# ProProject_DevBoard_20240716_2024-07-17.net
KiCad netlist of a schematic drawn in EasyEDA Pro
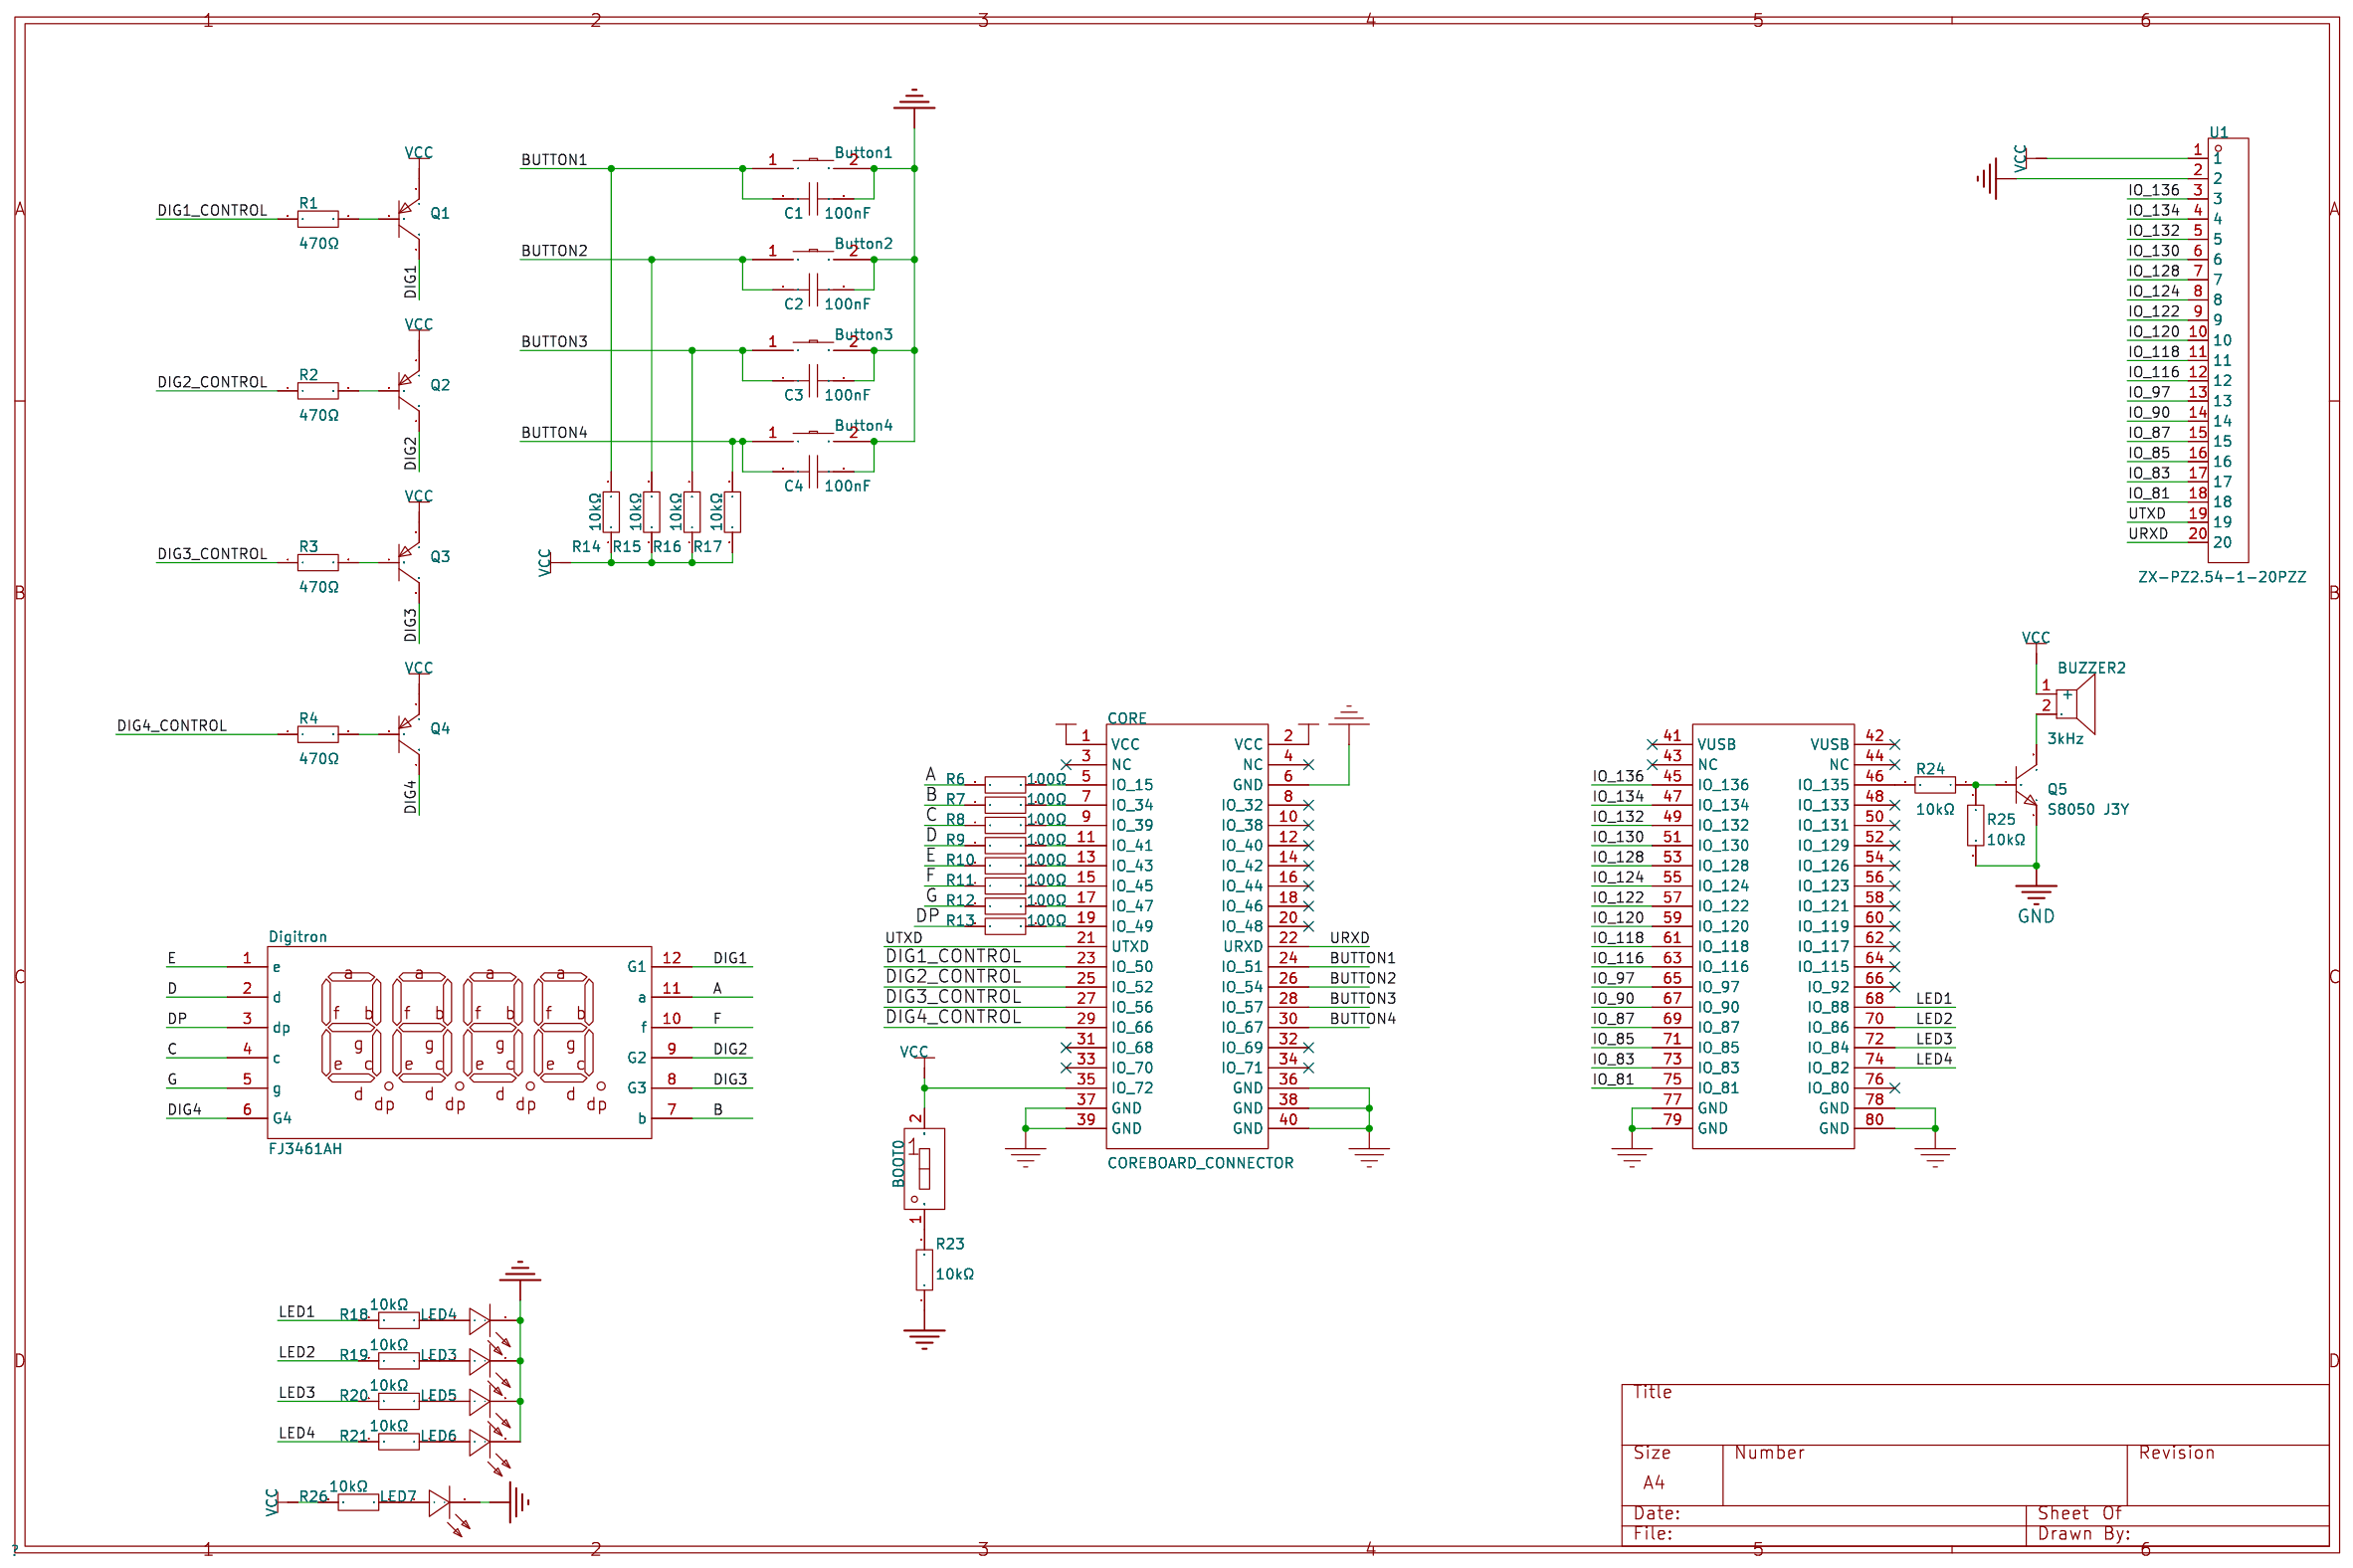
[diagram p0: schematic sheet]

(export (version "E")
  (design (tool "Eeschema 10.0.6"))
  (components
    (comp (ref "BOOT0")
      (value "DSIC01LS-P")
      (footprint "easyedapro:SW-SMD_2P-L3.5-W6.2-P2.54-LS9.8")
      (description "类型:平拨,凸起式;电路结构:单刀单掷;开关位数:1位;额定电流:25mA;额定电压:24V;使用寿命:3千次;颜色:黑色;")
      (fields (field (name "Manufacturer") "XKB Connectivity(中国星坤)"))
      (libsource (lib "easyedapro") (part "DSIC01LS-P_C600988"))
    )
    (comp (ref "Button1")
      (value "TS-1101-C-W")
      (footprint "easyedapro:SW-SMD_L6.0-W3.3-LS8.0")
      (fields (field (name "Manufacturer") "XKB Connectivity(中国星坤)"))
      (libsource (lib "easyedapro") (part "TS-1101-C-W"))
    )
    (comp (ref "Button2")
      (value "TS-1101-C-W")
      (footprint "easyedapro:SW-SMD_L6.0-W3.3-LS8.0")
      (fields (field (name "Manufacturer") "XKB Connectivity(中国星坤)"))
      (libsource (lib "easyedapro") (part "TS-1101-C-W"))
    )
    (comp (ref "Button3")
      (value "TS-1101-C-W")
      (footprint "easyedapro:SW-SMD_L6.0-W3.3-LS8.0")
      (fields (field (name "Manufacturer") "XKB Connectivity(中国星坤)"))
      (libsource (lib "easyedapro") (part "TS-1101-C-W"))
    )
    (comp (ref "Button4")
      (value "TS-1101-C-W")
      (footprint "easyedapro:SW-SMD_L6.0-W3.3-LS8.0")
      (fields (field (name "Manufacturer") "XKB Connectivity(中国星坤)"))
      (libsource (lib "easyedapro") (part "TS-1101-C-W"))
    )
    (comp (ref "BUZZER2")
      (value "3kHz")
      (footprint "easyedapro:BUZ-TH_BD9.6-P5.00-D0.7-FD")
      (description "驱动方式:有源(内含驱动线路);构造类型:电磁式;频率:3kHz;声压(SPL):85dB;")
      (fields (field (name "Manufacturer Part") "HNB09A05") (field (name "Manufacturer") "华能"))
      (libsource (lib "easyedapro") (part "HNB09A05"))
    )
    (comp (ref "C1")
      (value "100nF")
      (footprint "easyedapro:C0603")
      (description "容值:100nF;精度:±10%;额定电压:50V;材质(温度系数):X7R;")
      (fields
        (field (name "Manufacturer Part") "CC0603KRX7R9BB104")
        (field (name "Manufacturer") "YAGEO(国巨)")
      )
      (libsource (lib "easyedapro") (part "CC0603KRX7R9BB104"))
    )
    (comp (ref "C2")
      (value "100nF")
      (footprint "easyedapro:C0603")
      (description "容值:100nF;精度:±10%;额定电压:50V;材质(温度系数):X7R;")
      (fields
        (field (name "Manufacturer Part") "CC0603KRX7R9BB104")
        (field (name "Manufacturer") "YAGEO(国巨)")
      )
      (libsource (lib "easyedapro") (part "CC0603KRX7R9BB104"))
    )
    (comp (ref "C3")
      (value "100nF")
      (footprint "easyedapro:C0603")
      (description "容值:100nF;精度:±10%;额定电压:50V;材质(温度系数):X7R;")
      (fields
        (field (name "Manufacturer Part") "CC0603KRX7R9BB104")
        (field (name "Manufacturer") "YAGEO(国巨)")
      )
      (libsource (lib "easyedapro") (part "CC0603KRX7R9BB104"))
    )
    (comp (ref "C4")
      (value "100nF")
      (footprint "easyedapro:C0603")
      (description "容值:100nF;精度:±10%;额定电压:50V;材质(温度系数):X7R;")
      (fields
        (field (name "Manufacturer Part") "CC0603KRX7R9BB104")
        (field (name "Manufacturer") "YAGEO(国巨)")
      )
      (libsource (lib "easyedapro") (part "CC0603KRX7R9BB104"))
    )
    (comp (ref "CORE")
      (value "COREBOARD_CONNECTOR")
      (libsource (lib "easyedapro") (part "COREBOARD_CONNECTOR"))
    )
    (comp (ref "Digitron")
      (value "FJ3461AH")
      (footprint "easyedapro:LED-SEG-TH_12P-L30.0-W14.0-P2.54-S10.16-BL")
      (description "数码管位数:4位;功耗:-;发光颜色:红色;LED极性:共阴极;数字/字母大小(英寸):0.36;")
      (fields (field (name "Manufacturer") "志浩"))
      (libsource (lib "easyedapro") (part "FJ3461AH"))
    )
    (comp (ref "LED3")
      (value "NCD0805B2")
      (footprint "easyedapro:LED0805-R-RD")
      (fields (field (name "Manufacturer") "国星光电"))
      (libsource (lib "easyedapro") (part "FC-A2012BK-470H2"))
    )
    (comp (ref "LED4")
      (value "NCD0805B2")
      (footprint "easyedapro:LED0805-R-RD")
      (fields (field (name "Manufacturer") "国星光电"))
      (libsource (lib "easyedapro") (part "FC-A2012BK-470H2"))
    )
    (comp (ref "LED5")
      (value "NCD0805B2")
      (footprint "easyedapro:LED0805-R-RD")
      (fields (field (name "Manufacturer") "国星光电"))
      (libsource (lib "easyedapro") (part "FC-A2012BK-470H2"))
    )
    (comp (ref "LED6")
      (value "NCD0805B2")
      (footprint "easyedapro:LED0805-R-RD")
      (fields (field (name "Manufacturer") "国星光电"))
      (libsource (lib "easyedapro") (part "FC-A2012BK-470H2"))
    )
    (comp (ref "LED7")
      (value "NCD0805B2")
      (footprint "easyedapro:LED0805-R-RD")
      (fields (field (name "Manufacturer") "国星光电"))
      (libsource (lib "easyedapro") (part "FC-A2012BK-470H2"))
    )
    (comp (ref "Q1")
      (value "~")
      (footprint "easyedapro:S8550P_SOT")
      (libsource (lib "easyedapro") (part "PNP"))
    )
    (comp (ref "Q2")
      (value "~")
      (footprint "easyedapro:S8550P_SOT")
      (libsource (lib "easyedapro") (part "PNP"))
    )
    (comp (ref "Q3")
      (value "~")
      (footprint "easyedapro:S8550P_SOT")
      (libsource (lib "easyedapro") (part "PNP"))
    )
    (comp (ref "Q4")
      (value "~")
      (footprint "easyedapro:S8550P_SOT")
      (libsource (lib "easyedapro") (part "PNP"))
    )
    (comp (ref "Q5")
      (value "S8050 J3Y")
      (footprint "easyedapro:SOT-23-3_L3.0-W1.7-P0.95-LS2.9-BR")
      (description "晶体管类型:NPN;集射极击穿电压(Vceo):25V;集电极电流(Ic):500mA;功率(Pd):300mW;直流电流增益(hFE@Ic,Vce):200@50mA,1V;")
      (fields (field (name "Manufacturer") "CJ(江苏长电/长晶)"))
      (libsource (lib "easyedapro") (part "S8050_C2146"))
    )
    (comp (ref "R1")
      (value "470Ω")
      (footprint "easyedapro:R0603")
      (description "电阻类型:厚膜电阻;阻值:470Ω;精度:±1%;功率:100mW;最大工作电压:75V;温度系数:±100ppm/°C;")
      (fields
        (field (name "Manufacturer Part") "0603WAF4700T5E")
        (field (name "Manufacturer") "UNI-ROYAL(厚声)")
      )
      (libsource (lib "easyedapro") (part "0603WAF4700T5E"))
    )
    (comp (ref "R2")
      (value "470Ω")
      (footprint "easyedapro:R0603")
      (description "电阻类型:厚膜电阻;阻值:470Ω;精度:±1%;功率:100mW;最大工作电压:75V;温度系数:±100ppm/°C;")
      (fields
        (field (name "Manufacturer Part") "0603WAF4700T5E")
        (field (name "Manufacturer") "UNI-ROYAL(厚声)")
      )
      (libsource (lib "easyedapro") (part "0603WAF4700T5E"))
    )
    (comp (ref "R3")
      (value "470Ω")
      (footprint "easyedapro:R0603")
      (description "电阻类型:厚膜电阻;阻值:470Ω;精度:±1%;功率:100mW;最大工作电压:75V;温度系数:±100ppm/°C;")
      (fields
        (field (name "Manufacturer Part") "0603WAF4700T5E")
        (field (name "Manufacturer") "UNI-ROYAL(厚声)")
      )
      (libsource (lib "easyedapro") (part "0603WAF4700T5E"))
    )
    (comp (ref "R4")
      (value "470Ω")
      (footprint "easyedapro:R0603")
      (description "电阻类型:厚膜电阻;阻值:470Ω;精度:±1%;功率:100mW;最大工作电压:75V;温度系数:±100ppm/°C;")
      (fields
        (field (name "Manufacturer Part") "0603WAF4700T5E")
        (field (name "Manufacturer") "UNI-ROYAL(厚声)")
      )
      (libsource (lib "easyedapro") (part "0603WAF4700T5E"))
    )
    (comp (ref "R6")
      (value "100Ω")
      (footprint "easyedapro:R0603")
      (description "电阻类型:厚膜电阻;阻值:100Ω;精度:±1%;功率:100mW;最大工作电压:75V;温度系数:±200ppm/°C;")
      (fields
        (field (name "Manufacturer Part") "0603WAF1000T5E")
        (field (name "Manufacturer") "UNI-ROYAL(厚声)")
      )
      (libsource (lib "easyedapro") (part "0603WAF1000T5E"))
    )
    (comp (ref "R7")
      (value "100Ω")
      (footprint "easyedapro:R0603")
      (description "电阻类型:厚膜电阻;阻值:100Ω;精度:±1%;功率:100mW;最大工作电压:75V;温度系数:±200ppm/°C;")
      (fields
        (field (name "Manufacturer Part") "0603WAF1000T5E")
        (field (name "Manufacturer") "UNI-ROYAL(厚声)")
      )
      (libsource (lib "easyedapro") (part "0603WAF1000T5E"))
    )
    (comp (ref "R8")
      (value "100Ω")
      (footprint "easyedapro:R0603")
      (description "电阻类型:厚膜电阻;阻值:100Ω;精度:±1%;功率:100mW;最大工作电压:75V;温度系数:±200ppm/°C;")
      (fields
        (field (name "Manufacturer Part") "0603WAF1000T5E")
        (field (name "Manufacturer") "UNI-ROYAL(厚声)")
      )
      (libsource (lib "easyedapro") (part "0603WAF1000T5E"))
    )
    (comp (ref "R9")
      (value "100Ω")
      (footprint "easyedapro:R0603")
      (description "电阻类型:厚膜电阻;阻值:100Ω;精度:±1%;功率:100mW;最大工作电压:75V;温度系数:±200ppm/°C;")
      (fields
        (field (name "Manufacturer Part") "0603WAF1000T5E")
        (field (name "Manufacturer") "UNI-ROYAL(厚声)")
      )
      (libsource (lib "easyedapro") (part "0603WAF1000T5E"))
    )
    (comp (ref "R10")
      (value "100Ω")
      (footprint "easyedapro:R0603")
      (description "电阻类型:厚膜电阻;阻值:100Ω;精度:±1%;功率:100mW;最大工作电压:75V;温度系数:±200ppm/°C;")
      (fields
        (field (name "Manufacturer Part") "0603WAF1000T5E")
        (field (name "Manufacturer") "UNI-ROYAL(厚声)")
      )
      (libsource (lib "easyedapro") (part "0603WAF1000T5E"))
    )
    (comp (ref "R11")
      (value "100Ω")
      (footprint "easyedapro:R0603")
      (description "电阻类型:厚膜电阻;阻值:100Ω;精度:±1%;功率:100mW;最大工作电压:75V;温度系数:±200ppm/°C;")
      (fields
        (field (name "Manufacturer Part") "0603WAF1000T5E")
        (field (name "Manufacturer") "UNI-ROYAL(厚声)")
      )
      (libsource (lib "easyedapro") (part "0603WAF1000T5E"))
    )
    (comp (ref "R12")
      (value "100Ω")
      (footprint "easyedapro:R0603")
      (description "电阻类型:厚膜电阻;阻值:100Ω;精度:±1%;功率:100mW;最大工作电压:75V;温度系数:±200ppm/°C;")
      (fields
        (field (name "Manufacturer Part") "0603WAF1000T5E")
        (field (name "Manufacturer") "UNI-ROYAL(厚声)")
      )
      (libsource (lib "easyedapro") (part "0603WAF1000T5E"))
    )
    (comp (ref "R13")
      (value "100Ω")
      (footprint "easyedapro:R0603")
      (description "电阻类型:厚膜电阻;阻值:100Ω;精度:±1%;功率:100mW;最大工作电压:75V;温度系数:±200ppm/°C;")
      (fields
        (field (name "Manufacturer Part") "0603WAF1000T5E")
        (field (name "Manufacturer") "UNI-ROYAL(厚声)")
      )
      (libsource (lib "easyedapro") (part "0603WAF1000T5E"))
    )
    (comp (ref "R14")
      (value "10kΩ")
      (footprint "easyedapro:R0603")
      (description "电阻类型:厚膜电阻;阻值:10kΩ;精度:±1%;功率:100mW;最大工作电压:75V;温度系数:±100ppm/°C;")
      (fields
        (field (name "Manufacturer Part") "0603WAF1002T5E")
        (field (name "Manufacturer") "UNI-ROYAL(厚声)")
      )
      (libsource (lib "easyedapro") (part "0603WAF1002T5E"))
    )
    (comp (ref "R15")
      (value "10kΩ")
      (footprint "easyedapro:R0603")
      (description "电阻类型:厚膜电阻;阻值:10kΩ;精度:±1%;功率:100mW;最大工作电压:75V;温度系数:±100ppm/°C;")
      (fields
        (field (name "Manufacturer Part") "0603WAF1002T5E")
        (field (name "Manufacturer") "UNI-ROYAL(厚声)")
      )
      (libsource (lib "easyedapro") (part "0603WAF1002T5E"))
    )
    (comp (ref "R16")
      (value "10kΩ")
      (footprint "easyedapro:R0603")
      (description "电阻类型:厚膜电阻;阻值:10kΩ;精度:±1%;功率:100mW;最大工作电压:75V;温度系数:±100ppm/°C;")
      (fields
        (field (name "Manufacturer Part") "0603WAF1002T5E")
        (field (name "Manufacturer") "UNI-ROYAL(厚声)")
      )
      (libsource (lib "easyedapro") (part "0603WAF1002T5E"))
    )
    (comp (ref "R17")
      (value "10kΩ")
      (footprint "easyedapro:R0603")
      (description "电阻类型:厚膜电阻;阻值:10kΩ;精度:±1%;功率:100mW;最大工作电压:75V;温度系数:±100ppm/°C;")
      (fields
        (field (name "Manufacturer Part") "0603WAF1002T5E")
        (field (name "Manufacturer") "UNI-ROYAL(厚声)")
      )
      (libsource (lib "easyedapro") (part "0603WAF1002T5E"))
    )
    (comp (ref "R18")
      (value "10kΩ")
      (footprint "easyedapro:R0603")
      (description "电阻类型:厚膜电阻;阻值:10kΩ;精度:±1%;功率:100mW;最大工作电压:75V;温度系数:±100ppm/°C;")
      (fields
        (field (name "Manufacturer Part") "0603WAF1002T5E")
        (field (name "Manufacturer") "UNI-ROYAL(厚声)")
      )
      (libsource (lib "easyedapro") (part "0603WAF1002T5E"))
    )
    (comp (ref "R19")
      (value "10kΩ")
      (footprint "easyedapro:R0603")
      (description "电阻类型:厚膜电阻;阻值:10kΩ;精度:±1%;功率:100mW;最大工作电压:75V;温度系数:±100ppm/°C;")
      (fields
        (field (name "Manufacturer Part") "0603WAF1002T5E")
        (field (name "Manufacturer") "UNI-ROYAL(厚声)")
      )
      (libsource (lib "easyedapro") (part "0603WAF1002T5E"))
    )
    (comp (ref "R20")
      (value "10kΩ")
      (footprint "easyedapro:R0603")
      (description "电阻类型:厚膜电阻;阻值:10kΩ;精度:±1%;功率:100mW;最大工作电压:75V;温度系数:±100ppm/°C;")
      (fields
        (field (name "Manufacturer Part") "0603WAF1002T5E")
        (field (name "Manufacturer") "UNI-ROYAL(厚声)")
      )
      (libsource (lib "easyedapro") (part "0603WAF1002T5E"))
    )
    (comp (ref "R21")
      (value "10kΩ")
      (footprint "easyedapro:R0603")
      (description "电阻类型:厚膜电阻;阻值:10kΩ;精度:±1%;功率:100mW;最大工作电压:75V;温度系数:±100ppm/°C;")
      (fields
        (field (name "Manufacturer Part") "0603WAF1002T5E")
        (field (name "Manufacturer") "UNI-ROYAL(厚声)")
      )
      (libsource (lib "easyedapro") (part "0603WAF1002T5E"))
    )
    (comp (ref "R23")
      (value "10kΩ")
      (footprint "easyedapro:R0603")
      (description "电阻类型:厚膜电阻;阻值:10kΩ;精度:±1%;功率:100mW;最大工作电压:75V;温度系数:±100ppm/°C;")
      (fields
        (field (name "Manufacturer Part") "0603WAF1002T5E")
        (field (name "Manufacturer") "UNI-ROYAL(厚声)")
      )
      (libsource (lib "easyedapro") (part "0603WAF1002T5E"))
    )
    (comp (ref "R24")
      (value "10kΩ")
      (footprint "easyedapro:R0805")
      (description "阻值:10kΩ;精度:±1%;功率:125mW;温度系数:±100ppm/°C;电阻类型:厚膜电阻;")
      (fields
        (field (name "Manufacturer Part") "0805W8F1002T5E")
        (field (name "Manufacturer") "UNI-ROYAL(厚声)")
      )
      (libsource (lib "easyedapro") (part "0805W8F1002T5E"))
    )
    (comp (ref "R25")
      (value "10kΩ")
      (footprint "easyedapro:R0805")
      (description "阻值:10kΩ;精度:±1%;功率:125mW;温度系数:±100ppm/°C;电阻类型:厚膜电阻;")
      (fields
        (field (name "Manufacturer Part") "0805W8F1002T5E")
        (field (name "Manufacturer") "UNI-ROYAL(厚声)")
      )
      (libsource (lib "easyedapro") (part "0805W8F1002T5E"))
    )
    (comp (ref "R26")
      (value "10kΩ")
      (footprint "easyedapro:R0603")
      (description "电阻类型:厚膜电阻;阻值:10kΩ;精度:±1%;功率:100mW;最大工作电压:75V;温度系数:±100ppm/°C;")
      (fields
        (field (name "Manufacturer Part") "0603WAF1002T5E")
        (field (name "Manufacturer") "UNI-ROYAL(厚声)")
      )
      (libsource (lib "easyedapro") (part "0603WAF1002T5E"))
    )
    (comp (ref "U1")
      (value "ZX-PZ2.54-1-20PZZ")
      (footprint "easyedapro:HDR-TH_20P-P2.54-V-M")
      (fields (field (name "Manufacturer") "Megastar(兆星)"))
      (libsource (lib "easyedapro") (part "ZX-PZ2.54-1-20PZZ"))
    )
  )
  (nets
    (net (code "1") (name "/A") (class "Default")
      (node (ref "Digitron") (pin "11") (pinfunction "a_11") (pintype "input"))
      (node (ref "R6") (pin "1") (pinfunction "1_1") (pintype "input"))
    )
    (net (code "2") (name "/B") (class "Default")
      (node (ref "Digitron") (pin "7") (pinfunction "b_7") (pintype "input"))
      (node (ref "R7") (pin "1") (pinfunction "1_1") (pintype "input"))
    )
    (net (code "3") (name "/BUTTON1") (class "Default")
      (node (ref "Button1") (pin "1") (pinfunction "1_1") (pintype "unspecified"))
      (node (ref "C1") (pin "1") (pinfunction "1_1") (pintype "unspecified"))
      (node (ref "CORE") (pin "24") (pinfunction "IO_51_24") (pintype "unspecified"))
      (node (ref "R14") (pin "2") (pinfunction "2_2") (pintype "input"))
    )
    (net (code "4") (name "/BUTTON2") (class "Default")
      (node (ref "Button2") (pin "1") (pinfunction "1_1") (pintype "unspecified"))
      (node (ref "C2") (pin "1") (pinfunction "1_1") (pintype "unspecified"))
      (node (ref "CORE") (pin "26") (pinfunction "IO_54_26") (pintype "unspecified"))
      (node (ref "R15") (pin "2") (pinfunction "2_2") (pintype "input"))
    )
    (net (code "5") (name "/BUTTON3") (class "Default")
      (node (ref "Button3") (pin "1") (pinfunction "1_1") (pintype "unspecified"))
      (node (ref "C3") (pin "1") (pinfunction "1_1") (pintype "unspecified"))
      (node (ref "CORE") (pin "28") (pinfunction "IO_57_28") (pintype "unspecified"))
      (node (ref "R16") (pin "2") (pinfunction "2_2") (pintype "input"))
    )
    (net (code "6") (name "/BUTTON4") (class "Default")
      (node (ref "Button4") (pin "1") (pinfunction "1_1") (pintype "unspecified"))
      (node (ref "C4") (pin "1") (pinfunction "1_1") (pintype "unspecified"))
      (node (ref "CORE") (pin "30") (pinfunction "IO_67_30") (pintype "unspecified"))
      (node (ref "R17") (pin "2") (pinfunction "2_2") (pintype "input"))
    )
    (net (code "7") (name "/C") (class "Default")
      (node (ref "Digitron") (pin "4") (pinfunction "c_4") (pintype "input"))
      (node (ref "R8") (pin "1") (pinfunction "1_1") (pintype "input"))
    )
    (net (code "8") (name "/D") (class "Default")
      (node (ref "Digitron") (pin "2") (pinfunction "d_2") (pintype "input"))
      (node (ref "R9") (pin "1") (pinfunction "1_1") (pintype "input"))
    )
    (net (code "9") (name "/DIG1") (class "Default")
      (node (ref "Digitron") (pin "12") (pinfunction "G1_12") (pintype "input"))
      (node (ref "Q1") (pin "3") (pinfunction "C_3") (pintype "input"))
    )
    (net (code "10") (name "/DIG1_CONTROL") (class "Default")
      (node (ref "CORE") (pin "23") (pinfunction "IO_50_23") (pintype "unspecified"))
      (node (ref "R1") (pin "2") (pinfunction "2_2") (pintype "input"))
    )
    (net (code "11") (name "/DIG2") (class "Default")
      (node (ref "Digitron") (pin "9") (pinfunction "G2_9") (pintype "input"))
      (node (ref "Q2") (pin "3") (pinfunction "C_3") (pintype "input"))
    )
    (net (code "12") (name "/DIG2_CONTROL") (class "Default")
      (node (ref "CORE") (pin "25") (pinfunction "IO_52_25") (pintype "unspecified"))
      (node (ref "R2") (pin "1") (pinfunction "1_1") (pintype "input"))
    )
    (net (code "13") (name "/DIG3") (class "Default")
      (node (ref "Digitron") (pin "8") (pinfunction "G3_8") (pintype "input"))
      (node (ref "Q3") (pin "3") (pinfunction "C_3") (pintype "input"))
    )
    (net (code "14") (name "/DIG3_CONTROL") (class "Default")
      (node (ref "CORE") (pin "27") (pinfunction "IO_56_27") (pintype "unspecified"))
      (node (ref "R3") (pin "1") (pinfunction "1_1") (pintype "input"))
    )
    (net (code "15") (name "/DIG4") (class "Default")
      (node (ref "Digitron") (pin "6") (pinfunction "G4_6") (pintype "input"))
      (node (ref "Q4") (pin "3") (pinfunction "C_3") (pintype "input"))
    )
    (net (code "16") (name "/DIG4_CONTROL") (class "Default")
      (node (ref "CORE") (pin "29") (pinfunction "IO_66_29") (pintype "unspecified"))
      (node (ref "R4") (pin "1") (pinfunction "1_1") (pintype "input"))
    )
    (net (code "17") (name "/DP") (class "Default")
      (node (ref "Digitron") (pin "3") (pinfunction "dp_3") (pintype "input"))
      (node (ref "R13") (pin "1") (pinfunction "1_1") (pintype "input"))
    )
    (net (code "18") (name "/E") (class "Default")
      (node (ref "Digitron") (pin "1") (pinfunction "e_1") (pintype "input"))
      (node (ref "R10") (pin "1") (pinfunction "1_1") (pintype "input"))
    )
    (net (code "19") (name "/F") (class "Default")
      (node (ref "Digitron") (pin "10") (pinfunction "f_10") (pintype "input"))
      (node (ref "R11") (pin "1") (pinfunction "1_1") (pintype "input"))
    )
    (net (code "20") (name "/G") (class "Default")
      (node (ref "Digitron") (pin "5") (pinfunction "g_5") (pintype "input"))
      (node (ref "R12") (pin "1") (pinfunction "1_1") (pintype "input"))
    )
    (net (code "21") (name "/IO_81") (class "Default")
      (node (ref "CORE") (pin "75") (pinfunction "IO_81_75") (pintype "unspecified"))
      (node (ref "U1") (pin "18") (pinfunction "18_18") (pintype "unspecified"))
    )
    (net (code "22") (name "/IO_83") (class "Default")
      (node (ref "CORE") (pin "73") (pinfunction "IO_83_73") (pintype "unspecified"))
      (node (ref "U1") (pin "17") (pinfunction "17_17") (pintype "unspecified"))
    )
    (net (code "23") (name "/IO_85") (class "Default")
      (node (ref "CORE") (pin "71") (pinfunction "IO_85_71") (pintype "unspecified"))
      (node (ref "U1") (pin "16") (pinfunction "16_16") (pintype "unspecified"))
    )
    (net (code "24") (name "/IO_87") (class "Default")
      (node (ref "CORE") (pin "69") (pinfunction "IO_87_69") (pintype "unspecified"))
      (node (ref "U1") (pin "15") (pinfunction "15_15") (pintype "unspecified"))
    )
    (net (code "25") (name "/IO_90") (class "Default")
      (node (ref "CORE") (pin "67") (pinfunction "IO_90_67") (pintype "unspecified"))
      (node (ref "U1") (pin "14") (pinfunction "14_14") (pintype "unspecified"))
    )
    (net (code "26") (name "/IO_97") (class "Default")
      (node (ref "CORE") (pin "65") (pinfunction "IO_97_65") (pintype "unspecified"))
      (node (ref "U1") (pin "13") (pinfunction "13_13") (pintype "unspecified"))
    )
    (net (code "27") (name "/IO_116") (class "Default")
      (node (ref "CORE") (pin "63") (pinfunction "IO_116_63") (pintype "unspecified"))
      (node (ref "U1") (pin "12") (pinfunction "12_12") (pintype "unspecified"))
    )
    (net (code "28") (name "/IO_118") (class "Default")
      (node (ref "CORE") (pin "61") (pinfunction "IO_118_61") (pintype "unspecified"))
      (node (ref "U1") (pin "11") (pinfunction "11_11") (pintype "unspecified"))
    )
    (net (code "29") (name "/IO_120") (class "Default")
      (node (ref "CORE") (pin "59") (pinfunction "IO_120_59") (pintype "unspecified"))
      (node (ref "U1") (pin "10") (pinfunction "10_10") (pintype "unspecified"))
    )
    (net (code "30") (name "/IO_122") (class "Default")
      (node (ref "CORE") (pin "57") (pinfunction "IO_122_57") (pintype "unspecified"))
      (node (ref "U1") (pin "9") (pinfunction "9_9") (pintype "unspecified"))
    )
    (net (code "31") (name "/IO_124") (class "Default")
      (node (ref "CORE") (pin "55") (pinfunction "IO_124_55") (pintype "unspecified"))
      (node (ref "U1") (pin "8") (pinfunction "8_8") (pintype "unspecified"))
    )
    (net (code "32") (name "/IO_128") (class "Default")
      (node (ref "CORE") (pin "53") (pinfunction "IO_128_53") (pintype "unspecified"))
      (node (ref "U1") (pin "7") (pinfunction "7_7") (pintype "unspecified"))
    )
    (net (code "33") (name "/IO_130") (class "Default")
      (node (ref "CORE") (pin "51") (pinfunction "IO_130_51") (pintype "unspecified"))
      (node (ref "U1") (pin "6") (pinfunction "6_6") (pintype "unspecified"))
    )
    (net (code "34") (name "/IO_132") (class "Default")
      (node (ref "CORE") (pin "49") (pinfunction "IO_132_49") (pintype "unspecified"))
      (node (ref "U1") (pin "5") (pinfunction "5_5") (pintype "unspecified"))
    )
    (net (code "35") (name "/IO_134") (class "Default")
      (node (ref "CORE") (pin "47") (pinfunction "IO_134_47") (pintype "unspecified"))
      (node (ref "U1") (pin "4") (pinfunction "4_4") (pintype "unspecified"))
    )
    (net (code "36") (name "/IO_136") (class "Default")
      (node (ref "CORE") (pin "45") (pinfunction "IO_136_45") (pintype "unspecified"))
      (node (ref "U1") (pin "3") (pinfunction "3_3") (pintype "unspecified"))
    )
    (net (code "37") (name "/LED1") (class "Default")
      (node (ref "CORE") (pin "68") (pinfunction "IO_88_68") (pintype "unspecified"))
      (node (ref "R18") (pin "2") (pinfunction "2_2") (pintype "input"))
    )
    (net (code "38") (name "/LED2") (class "Default")
      (node (ref "CORE") (pin "70") (pinfunction "IO_86_70") (pintype "unspecified"))
      (node (ref "R19") (pin "2") (pinfunction "2_2") (pintype "input"))
    )
    (net (code "39") (name "/LED3") (class "Default")
      (node (ref "CORE") (pin "72") (pinfunction "IO_84_72") (pintype "unspecified"))
      (node (ref "R20") (pin "2") (pinfunction "2_2") (pintype "input"))
    )
    (net (code "40") (name "/LED4") (class "Default")
      (node (ref "CORE") (pin "74") (pinfunction "IO_82_74") (pintype "unspecified"))
      (node (ref "R21") (pin "2") (pinfunction "2_2") (pintype "input"))
    )
    (net (code "41") (name "/URXD") (class "Default")
      (node (ref "CORE") (pin "22") (pinfunction "URXD_22") (pintype "unspecified"))
      (node (ref "U1") (pin "20") (pinfunction "20_20") (pintype "unspecified"))
    )
    (net (code "42") (name "/UTXD") (class "Default")
      (node (ref "CORE") (pin "21") (pinfunction "UTXD_21") (pintype "unspecified"))
      (node (ref "U1") (pin "19") (pinfunction "19_19") (pintype "unspecified"))
    )
    (net (code "43") (name "GND") (class "Default")
      (node (ref "Button1") (pin "2") (pinfunction "2_2") (pintype "unspecified"))
      (node (ref "Button2") (pin "2") (pinfunction "2_2") (pintype "unspecified"))
      (node (ref "Button3") (pin "2") (pinfunction "2_2") (pintype "unspecified"))
      (node (ref "Button4") (pin "2") (pinfunction "2_2") (pintype "unspecified"))
      (node (ref "C1") (pin "2") (pinfunction "2_2") (pintype "unspecified"))
      (node (ref "C2") (pin "2") (pinfunction "2_2") (pintype "unspecified"))
      (node (ref "C3") (pin "2") (pinfunction "2_2") (pintype "unspecified"))
      (node (ref "C4") (pin "2") (pinfunction "2_2") (pintype "unspecified"))
      (node (ref "CORE") (pin "36") (pinfunction "GND_36") (pintype "unspecified"))
      (node (ref "CORE") (pin "37") (pinfunction "GND_37") (pintype "unspecified"))
      (node (ref "CORE") (pin "38") (pinfunction "GND_38") (pintype "unspecified"))
      (node (ref "CORE") (pin "39") (pinfunction "GND_39") (pintype "unspecified"))
      (node (ref "CORE") (pin "40") (pinfunction "GND_40") (pintype "unspecified"))
      (node (ref "CORE") (pin "6") (pinfunction "GND_6") (pintype "unspecified"))
      (node (ref "CORE") (pin "77") (pinfunction "GND_77") (pintype "unspecified"))
      (node (ref "CORE") (pin "78") (pinfunction "GND_78") (pintype "unspecified"))
      (node (ref "CORE") (pin "79") (pinfunction "GND_79") (pintype "unspecified"))
      (node (ref "CORE") (pin "80") (pinfunction "GND_80") (pintype "unspecified"))
      (node (ref "LED3") (pin "2") (pinfunction "-_2") (pintype "unspecified"))
      (node (ref "LED4") (pin "2") (pinfunction "-_2") (pintype "unspecified"))
      (node (ref "LED5") (pin "2") (pinfunction "-_2") (pintype "unspecified"))
      (node (ref "LED6") (pin "2") (pinfunction "-_2") (pintype "unspecified"))
      (node (ref "LED7") (pin "2") (pinfunction "-_2") (pintype "unspecified"))
      (node (ref "Q5") (pin "2") (pinfunction "E_2") (pintype "unspecified"))
      (node (ref "R23") (pin "1") (pinfunction "1_1") (pintype "input"))
      (node (ref "R25") (pin "2") (pinfunction "2_2") (pintype "input"))
      (node (ref "U1") (pin "2") (pinfunction "2_2") (pintype "unspecified"))
    )
    (net (code "44") (name "Net-(BOOT0-PIN1)") (class "Default")
      (node (ref "BOOT0") (pin "1") (pinfunction "PIN1_1") (pintype "unspecified"))
      (node (ref "R23") (pin "2") (pinfunction "2_2") (pintype "input"))
    )
    (net (code "45") (name "Net-(CORE-IO_15)") (class "Default")
      (node (ref "CORE") (pin "5") (pinfunction "IO_15_5") (pintype "unspecified"))
      (node (ref "R6") (pin "2") (pinfunction "2_2") (pintype "input"))
    )
    (net (code "46") (name "Net-(CORE-IO_34)") (class "Default")
      (node (ref "CORE") (pin "7") (pinfunction "IO_34_7") (pintype "unspecified"))
      (node (ref "R7") (pin "2") (pinfunction "2_2") (pintype "input"))
    )
    (net (code "47") (name "Net-(CORE-IO_39)") (class "Default")
      (node (ref "CORE") (pin "9") (pinfunction "IO_39_9") (pintype "unspecified"))
      (node (ref "R8") (pin "2") (pinfunction "2_2") (pintype "input"))
    )
    (net (code "48") (name "Net-(CORE-IO_41)") (class "Default")
      (node (ref "CORE") (pin "11") (pinfunction "IO_41_11") (pintype "unspecified"))
      (node (ref "R9") (pin "2") (pinfunction "2_2") (pintype "input"))
    )
    (net (code "49") (name "Net-(CORE-IO_43)") (class "Default")
      (node (ref "CORE") (pin "13") (pinfunction "IO_43_13") (pintype "unspecified"))
      (node (ref "R10") (pin "2") (pinfunction "2_2") (pintype "input"))
    )
    (net (code "50") (name "Net-(CORE-IO_45)") (class "Default")
      (node (ref "CORE") (pin "15") (pinfunction "IO_45_15") (pintype "unspecified"))
      (node (ref "R11") (pin "2") (pinfunction "2_2") (pintype "input"))
    )
    (net (code "51") (name "Net-(CORE-IO_47)") (class "Default")
      (node (ref "CORE") (pin "17") (pinfunction "IO_47_17") (pintype "unspecified"))
      (node (ref "R12") (pin "2") (pinfunction "2_2") (pintype "input"))
    )
    (net (code "52") (name "Net-(CORE-IO_49)") (class "Default")
      (node (ref "CORE") (pin "19") (pinfunction "IO_49_19") (pintype "unspecified"))
      (node (ref "R13") (pin "2") (pinfunction "2_2") (pintype "input"))
    )
    (net (code "53") (name "Net-(CORE-IO_135)") (class "Default")
      (node (ref "CORE") (pin "46") (pinfunction "IO_135_46") (pintype "unspecified"))
      (node (ref "R24") (pin "2") (pinfunction "2_2") (pintype "input"))
    )
    (net (code "54") (name "Net-(LED3-+)") (class "Default")
      (node (ref "LED3") (pin "1") (pinfunction "+_1") (pintype "unspecified"))
      (node (ref "R19") (pin "1") (pinfunction "1_1") (pintype "input"))
    )
    (net (code "55") (name "Net-(LED4-+)") (class "Default")
      (node (ref "LED4") (pin "1") (pinfunction "+_1") (pintype "unspecified"))
      (node (ref "R18") (pin "1") (pinfunction "1_1") (pintype "input"))
    )
    (net (code "56") (name "Net-(LED5-+)") (class "Default")
      (node (ref "LED5") (pin "1") (pinfunction "+_1") (pintype "unspecified"))
      (node (ref "R20") (pin "1") (pinfunction "1_1") (pintype "input"))
    )
    (net (code "57") (name "Net-(LED6-+)") (class "Default")
      (node (ref "LED6") (pin "1") (pinfunction "+_1") (pintype "unspecified"))
      (node (ref "R21") (pin "1") (pinfunction "1_1") (pintype "input"))
    )
    (net (code "58") (name "Net-(LED7-+)") (class "Default")
      (node (ref "LED7") (pin "1") (pinfunction "+_1") (pintype "unspecified"))
      (node (ref "R26") (pin "1") (pinfunction "1_1") (pintype "input"))
    )
    (net (code "59") (name "Net-(Q1-B)") (class "Default")
      (node (ref "Q1") (pin "1") (pinfunction "B_1") (pintype "input"))
      (node (ref "R1") (pin "1") (pinfunction "1_1") (pintype "input"))
    )
    (net (code "60") (name "Net-(Q2-B)") (class "Default")
      (node (ref "Q2") (pin "1") (pinfunction "B_1") (pintype "input"))
      (node (ref "R2") (pin "2") (pinfunction "2_2") (pintype "input"))
    )
    (net (code "61") (name "Net-(Q3-B)") (class "Default")
      (node (ref "Q3") (pin "1") (pinfunction "B_1") (pintype "input"))
      (node (ref "R3") (pin "2") (pinfunction "2_2") (pintype "input"))
    )
    (net (code "62") (name "Net-(Q4-B)") (class "Default")
      (node (ref "Q4") (pin "1") (pinfunction "B_1") (pintype "input"))
      (node (ref "R4") (pin "2") (pinfunction "2_2") (pintype "input"))
    )
    (net (code "63") (name "Net-(Q5-B)") (class "Default")
      (node (ref "Q5") (pin "1") (pinfunction "B_1") (pintype "unspecified"))
      (node (ref "R24") (pin "1") (pinfunction "1_1") (pintype "input"))
      (node (ref "R25") (pin "1") (pinfunction "1_1") (pintype "input"))
    )
    (net (code "64") (name "Net-(Q5-C)") (class "Default")
      (node (ref "BUZZER2") (pin "2") (pinfunction "2_2") (pintype "unspecified"))
      (node (ref "Q5") (pin "3") (pinfunction "C_3") (pintype "unspecified"))
    )
    (net (code "65") (name "VCC") (class "Default")
      (node (ref "BOOT0") (pin "2") (pinfunction "PIN2_2") (pintype "unspecified"))
      (node (ref "BUZZER2") (pin "1") (pinfunction "+_1") (pintype "unspecified"))
      (node (ref "CORE") (pin "1") (pinfunction "VCC_1") (pintype "unspecified"))
      (node (ref "CORE") (pin "2") (pinfunction "VCC_2") (pintype "unspecified"))
      (node (ref "CORE") (pin "35") (pinfunction "IO_72_35") (pintype "unspecified"))
      (node (ref "Q1") (pin "2") (pinfunction "E_2") (pintype "input"))
      (node (ref "Q2") (pin "2") (pinfunction "E_2") (pintype "input"))
      (node (ref "Q3") (pin "2") (pinfunction "E_2") (pintype "input"))
      (node (ref "Q4") (pin "2") (pinfunction "E_2") (pintype "input"))
      (node (ref "R14") (pin "1") (pinfunction "1_1") (pintype "input"))
      (node (ref "R15") (pin "1") (pinfunction "1_1") (pintype "input"))
      (node (ref "R16") (pin "1") (pinfunction "1_1") (pintype "input"))
      (node (ref "R17") (pin "1") (pinfunction "1_1") (pintype "input"))
      (node (ref "R26") (pin "2") (pinfunction "2_2") (pintype "input"))
      (node (ref "U1") (pin "1") (pinfunction "1_1") (pintype "unspecified"))
    )
    (net (code "66") (name "unconnected-(CORE-IO_32-Pad8)") (class "Default")
      (node (ref "CORE") (pin "8") (pinfunction "IO_32_8") (pintype "unspecified+no_connect"))
    )
    (net (code "67") (name "unconnected-(CORE-IO_38-Pad10)") (class "Default")
      (node (ref "CORE") (pin "10") (pinfunction "IO_38_10") (pintype "unspecified+no_connect"))
    )
    (net (code "68") (name "unconnected-(CORE-IO_40-Pad12)") (class "Default")
      (node (ref "CORE") (pin "12") (pinfunction "IO_40_12") (pintype "unspecified+no_connect"))
    )
    (net (code "69") (name "unconnected-(CORE-IO_42-Pad14)") (class "Default")
      (node (ref "CORE") (pin "14") (pinfunction "IO_42_14") (pintype "unspecified+no_connect"))
    )
    (net (code "70") (name "unconnected-(CORE-IO_44-Pad16)") (class "Default")
      (node (ref "CORE") (pin "16") (pinfunction "IO_44_16") (pintype "unspecified+no_connect"))
    )
    (net (code "71") (name "unconnected-(CORE-IO_46-Pad18)") (class "Default")
      (node (ref "CORE") (pin "18") (pinfunction "IO_46_18") (pintype "unspecified+no_connect"))
    )
    (net (code "72") (name "unconnected-(CORE-IO_48-Pad20)") (class "Default")
      (node (ref "CORE") (pin "20") (pinfunction "IO_48_20") (pintype "unspecified+no_connect"))
    )
    (net (code "73") (name "unconnected-(CORE-IO_68-Pad31)") (class "Default")
      (node (ref "CORE") (pin "31") (pinfunction "IO_68_31") (pintype "unspecified+no_connect"))
    )
    (net (code "74") (name "unconnected-(CORE-IO_69-Pad32)") (class "Default")
      (node (ref "CORE") (pin "32") (pinfunction "IO_69_32") (pintype "unspecified+no_connect"))
    )
    (net (code "75") (name "unconnected-(CORE-IO_70-Pad33)") (class "Default")
      (node (ref "CORE") (pin "33") (pinfunction "IO_70_33") (pintype "unspecified+no_connect"))
    )
    (net (code "76") (name "unconnected-(CORE-IO_71-Pad34)") (class "Default")
      (node (ref "CORE") (pin "34") (pinfunction "IO_71_34") (pintype "unspecified+no_connect"))
    )
    (net (code "77") (name "unconnected-(CORE-IO_80-Pad76)") (class "Default")
      (node (ref "CORE") (pin "76") (pinfunction "IO_80_76") (pintype "unspecified+no_connect"))
    )
    (net (code "78") (name "unconnected-(CORE-IO_92-Pad66)") (class "Default")
      (node (ref "CORE") (pin "66") (pinfunction "IO_92_66") (pintype "unspecified+no_connect"))
    )
    (net (code "79") (name "unconnected-(CORE-IO_115-Pad64)") (class "Default")
      (node (ref "CORE") (pin "64") (pinfunction "IO_115_64") (pintype "unspecified+no_connect"))
    )
    (net (code "80") (name "unconnected-(CORE-IO_117-Pad62)") (class "Default")
      (node (ref "CORE") (pin "62") (pinfunction "IO_117_62") (pintype "unspecified+no_connect"))
    )
    (net (code "81") (name "unconnected-(CORE-IO_119-Pad60)") (class "Default")
      (node (ref "CORE") (pin "60") (pinfunction "IO_119_60") (pintype "unspecified+no_connect"))
    )
    (net (code "82") (name "unconnected-(CORE-IO_121-Pad58)") (class "Default")
      (node (ref "CORE") (pin "58") (pinfunction "IO_121_58") (pintype "unspecified+no_connect"))
    )
    (net (code "83") (name "unconnected-(CORE-IO_123-Pad56)") (class "Default")
      (node (ref "CORE") (pin "56") (pinfunction "IO_123_56") (pintype "unspecified+no_connect"))
    )
    (net (code "84") (name "unconnected-(CORE-IO_126-Pad54)") (class "Default")
      (node (ref "CORE") (pin "54") (pinfunction "IO_126_54") (pintype "unspecified+no_connect"))
    )
    (net (code "85") (name "unconnected-(CORE-IO_129-Pad52)") (class "Default")
      (node (ref "CORE") (pin "52") (pinfunction "IO_129_52") (pintype "unspecified+no_connect"))
    )
    (net (code "86") (name "unconnected-(CORE-IO_131-Pad50)") (class "Default")
      (node (ref "CORE") (pin "50") (pinfunction "IO_131_50") (pintype "unspecified+no_connect"))
    )
    (net (code "87") (name "unconnected-(CORE-IO_133-Pad48)") (class "Default")
      (node (ref "CORE") (pin "48") (pinfunction "IO_133_48") (pintype "unspecified+no_connect"))
    )
    (net (code "88") (name "unconnected-(CORE-NC-Pad3)") (class "Default")
      (node (ref "CORE") (pin "3") (pinfunction "NC_3") (pintype "unspecified+no_connect"))
    )
    (net (code "89") (name "unconnected-(CORE-NC-Pad4)") (class "Default")
      (node (ref "CORE") (pin "4") (pinfunction "NC_4") (pintype "unspecified+no_connect"))
    )
    (net (code "90") (name "unconnected-(CORE-NC-Pad43)") (class "Default")
      (node (ref "CORE") (pin "43") (pinfunction "NC_43") (pintype "unspecified+no_connect"))
    )
    (net (code "91") (name "unconnected-(CORE-NC-Pad44)") (class "Default")
      (node (ref "CORE") (pin "44") (pinfunction "NC_44") (pintype "unspecified+no_connect"))
    )
    (net (code "92") (name "unconnected-(CORE-VUSB-Pad41)") (class "Default")
      (node (ref "CORE") (pin "41") (pinfunction "VUSB_41") (pintype "unspecified+no_connect"))
    )
    (net (code "93") (name "unconnected-(CORE-VUSB-Pad42)") (class "Default")
      (node (ref "CORE") (pin "42") (pinfunction "VUSB_42") (pintype "unspecified+no_connect"))
    )
  )
)
